# AICatRope_V1_2.net
KiCad netlist of a schematic drawn in Altium Designer
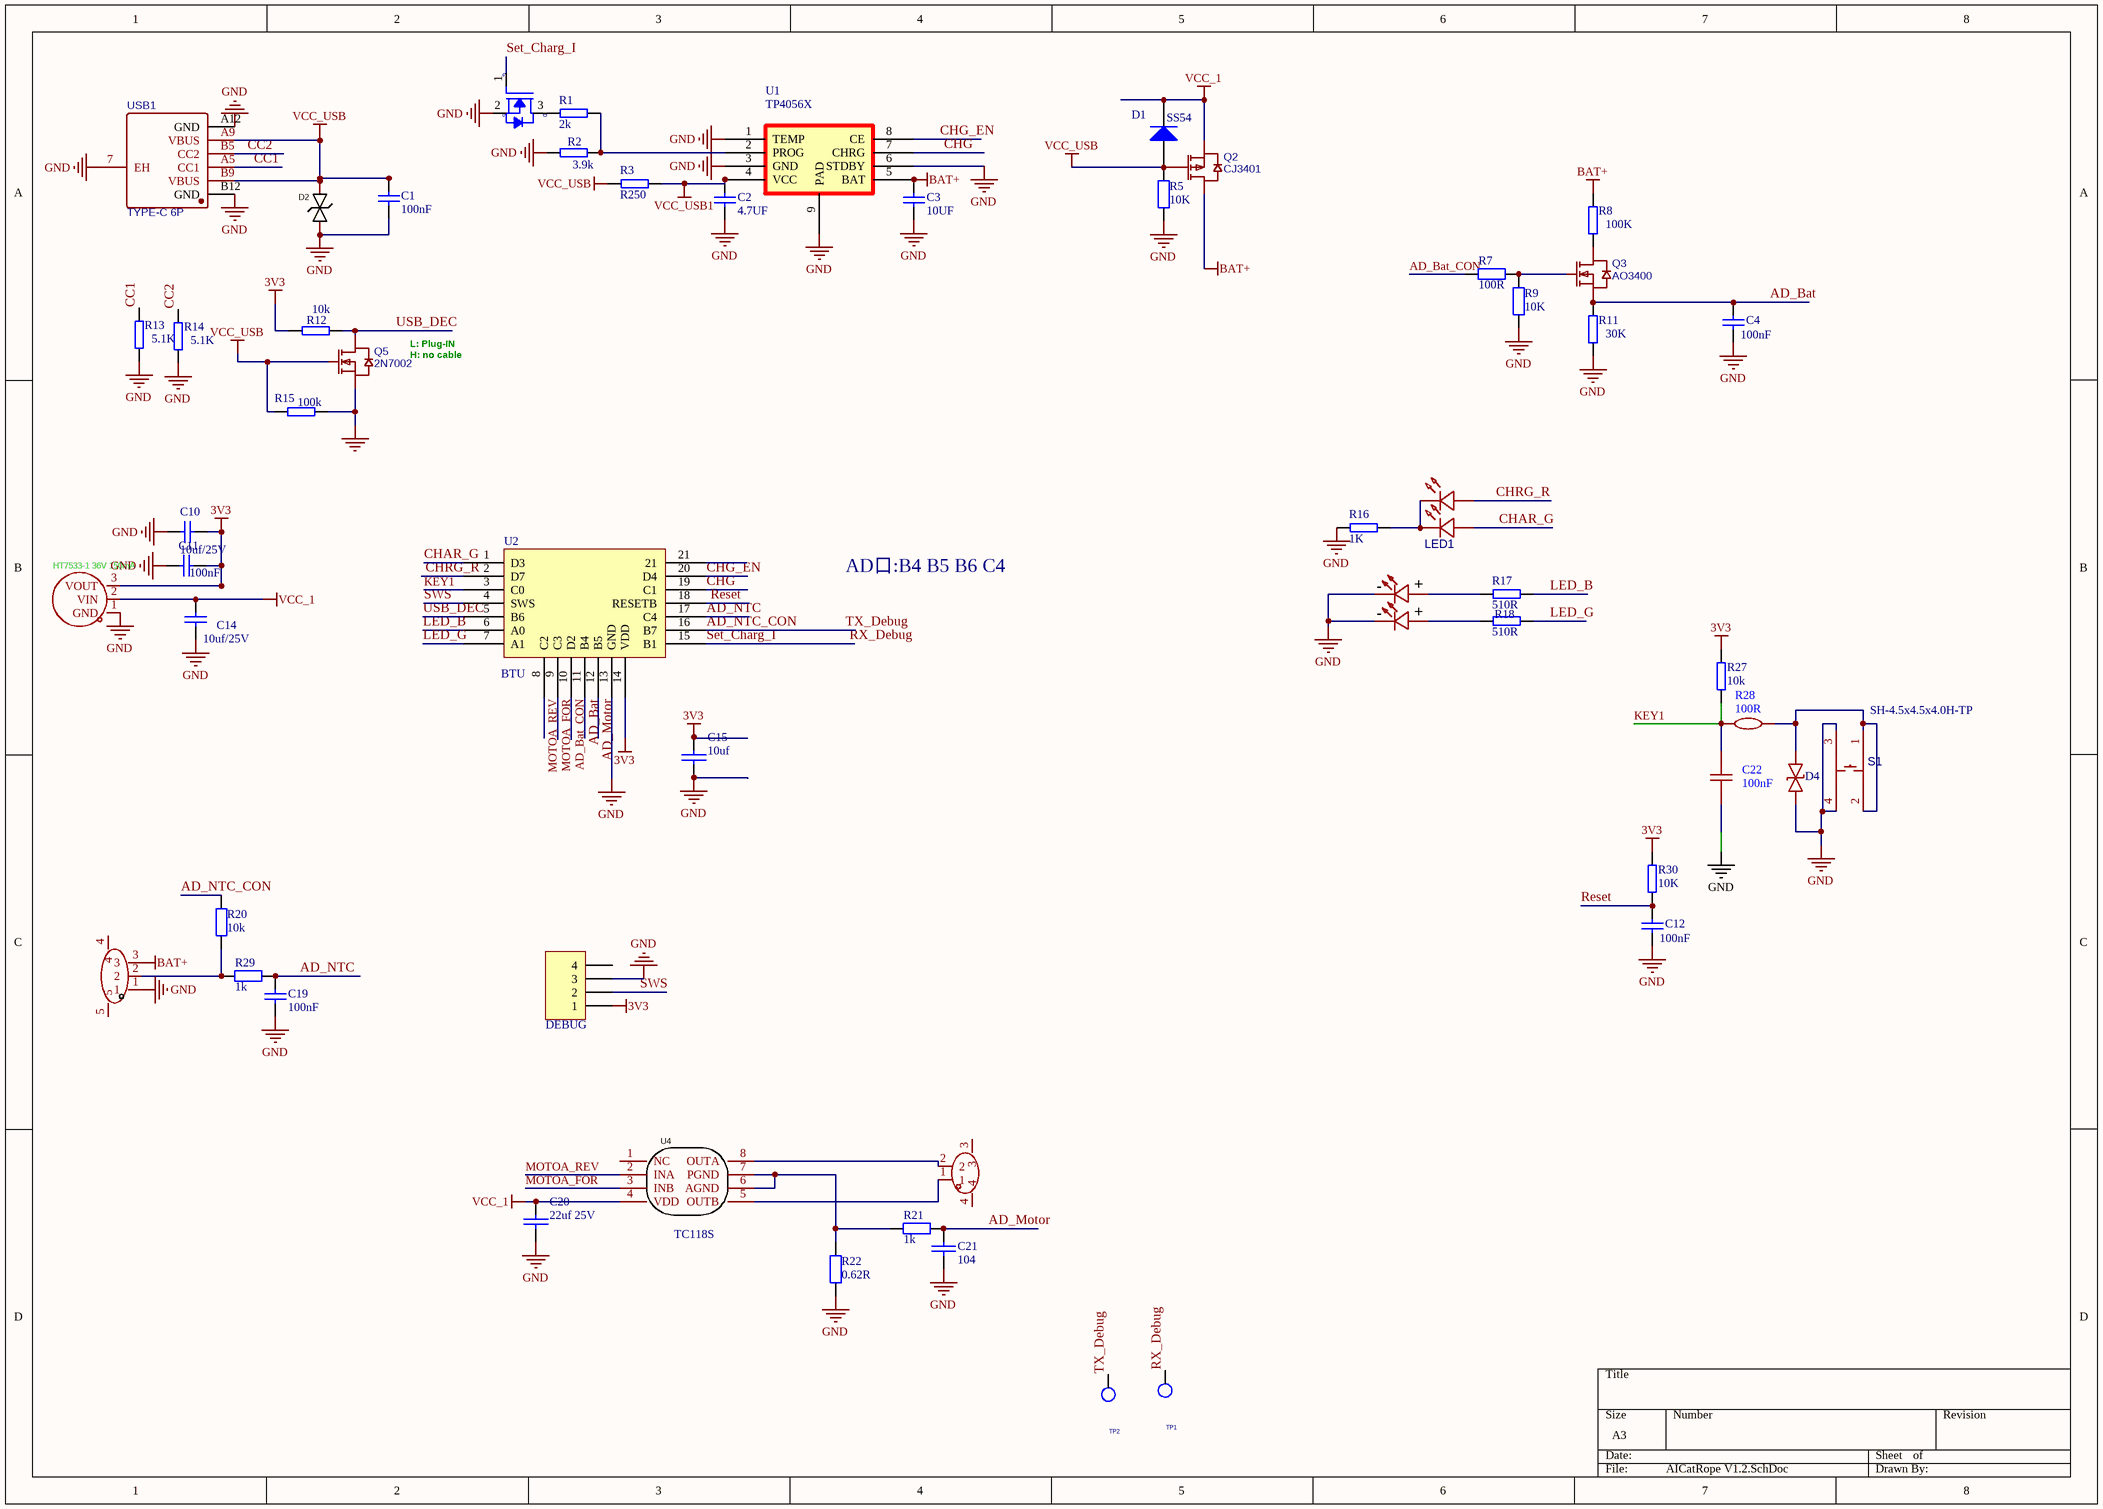
[diagram p0: AICatRope V1.2.SchDoc]

(export (version "E")
  (design (tool "Eeschema 10.0.6"))
  (components
    (comp (ref "BAT1")
      (value "BX-PH2.0-3PWT")
      (footprint "CONN-SMD_2.0-3PLT")
      (libsource (lib "altium-import") (part "root_2_BX-PH2.0-3PWT_"))
    )
    (comp (ref "C1") (value "100nF") (footprint "0603_C") (libsource (lib "DIY") (part "CAP")))
    (comp (ref "C2") (value "4.7UF") (footprint "0603_c") (libsource (lib "DIY") (part "CAP")))
    (comp (ref "C3") (value "10UF") (footprint "0603_c") (libsource (lib "DIY") (part "CAP")))
    (comp (ref "C4") (value "100nF") (footprint "0603_C") (libsource (lib "DIY") (part "CAP")))
    (comp (ref "C10")
      (value "10uf/25V")
      (footprint "0603_c")
      (description "无极电容")
      (libsource (lib "电容电阻电感保险") (part "Cap1"))
    )
    (comp (ref "C11") (value "100nF") (footprint "0603_C") (libsource (lib "DIY") (part "CAP")))
    (comp (ref "C12") (value "100nF") (footprint "0603_C") (libsource (lib "DIY") (part "CAP")))
    (comp (ref "C14")
      (value "10uf/25V")
      (footprint "0603_c")
      (description "无极电容")
      (libsource (lib "电容电阻电感保险") (part "Cap1"))
    )
    (comp (ref "C15")
      (value "10uf")
      (footprint "0603_c")
      (description "C-?-K-0603")
      (libsource (lib "HJ_AD_SchLib") (part "C-0603"))
    )
    (comp (ref "C19") (value "100nF") (footprint "0603_C") (libsource (lib "DIY") (part "CAP")))
    (comp (ref "C20")
      (value "22uf 25V")
      (footprint "0805_C")
      (description "C-?-K-0603")
      (libsource (lib "HJ_AD_SchLib") (part "C-0603"))
    )
    (comp (ref "C21")
      (value "104")
      (footprint "0603_C")
      (description "Capacitor")
      (libsource (lib "*") (part "CAP"))
    )
    (comp (ref "C22")
      (value "100nF")
      (footprint "0603_c")
      (libsource (lib "altium-import") (part "root_1_CAP_0603_"))
    )
    (comp (ref "CN1")
      (value "2.0-2P WT")
      (footprint "CONN-SMD_2.0-2PLT")
      (libsource (lib "altium-import") (part "root_2_mirrored_2.0-2P WT_"))
    )
    (comp (ref "D1")
      (value "SS54")
      (footprint "SMA")
      (description "High Conductance Fast Diode")
      (fields (field (name "PUBLISHER") "Altium Limited"))
      (libsource (lib "Miscellaneous Devices") (part "Diode 1N4148"))
    )
    (comp (ref "D2")
      (value "SMF6.0CA")
      (footprint "SOD-123 双向")
      (fields (field (name "MANUFACTURER PART") "SMF5.0CA"))
      (libsource (lib "altium-import") (part "root_1_SMF5.0CA_C726939_"))
    )
    (comp (ref "D4")
      (value "~")
      (footprint "SOD-523_L1.2-W0.8-LS1.6-RD")
      (fields (field (name "MANUFACTURER PART") "LESD5Z5.0CT1G"))
      (libsource (lib "altium-import") (part "root_1_LESD5Z5.0CT1G_"))
    )
    (comp (ref "LED1")
      (value "XL-3216SURUGC")
      (footprint "LED-SMD_4P-L3.2-W1.6-TL_XL-3216SURUGC")
      (libsource (lib "altium-import") (part "root_0_TJ-S2012SW8TCGLC2R2G-A5_"))
    )
    (comp (ref "LED2")
      (value "tj-s1615sw6tglcbg-a5")
      (footprint "LED-ARRAY-SMD_4P-L1.6-W1.5-TR-RD_TJ-S1615SW6TGLCRB-A5")
      (fields (field (name "MANUFACTURERPART") "TJ-S1615SW6TGLCBG-A5"))
      (libsource (lib "altium-import") (part "root_0_tj-s1615sw6tglcbg-a5_"))
    )
    (comp (ref "P1")
      (value "DEBUG")
      (footprint "SIP3-2.54")
      (description "Header, 4-Pin")
      (fields (field (name "PUBLISHER") "Altium Limited"))
      (libsource (lib "Miscellaneous Connectors") (part "Header 4"))
    )
    (comp (ref "Q1") (value "2N7002") (footprint "SOT-23") (libsource (lib "*") (part "AO3400_SOT23")))
    (comp (ref "Q2")
      (value "CJ3401")
      (footprint "SOT-23")
      (fields (field (name "BOM_SUPPLIER PART") "C13799"))
      (libsource (lib "altium-import") (part "root_2_mirrored_CJ3401_"))
    )
    (comp (ref "Q3")
      (value "AO3400")
      (footprint "SOT-23")
      (fields
        (field (name "BOM_SUPPLIER PART") "C2890442")
        (field (name "BOM_MANUFACTURER PART") "JMTL3400A")
        (field (name "CONTRIBUTOR") "LCSC")
      )
      (libsource (lib "altium-import") (part "root_0_JMTL3400A_"))
    )
    (comp (ref "Q5")
      (value "2N7002")
      (footprint "SOT-23")
      (fields
        (field (name "BOM_SUPPLIER PART") "C2890442")
        (field (name "BOM_MANUFACTURER PART") "JMTL3400A")
        (field (name "CONTRIBUTOR") "LCSC")
      )
      (libsource (lib "altium-import") (part "root_0_JMTL3400A_"))
    )
    (comp (ref "R1") (value "2k") (footprint "0603_R") (libsource (lib "DIY") (part "RES")))
    (comp (ref "R2") (value "3.9k") (footprint "0603_R") (libsource (lib "DIY") (part "RES")))
    (comp (ref "R3") (value "R250") (footprint "1206_R") (libsource (lib "DIY") (part "RES")))
    (comp (ref "R5")
      (value "10K")
      (footprint "0603_R")
      (description "Resistor")
      (fields (field (name "PUBLISHER") "Altium Limited"))
      (libsource (lib "") (part "Res2_2"))
    )
    (comp (ref "R7")
      (value "100R")
      (footprint "0603_r")
      (description "Resistor")
      (fields (field (name "PUBLISHER") "Altium Limited"))
      (libsource (lib "") (part "Res2_3"))
    )
    (comp (ref "R8") (value "100K") (footprint "0603_R") (libsource (lib "DIY") (part "RES")))
    (comp (ref "R9")
      (value "10K")
      (footprint "0603_r")
      (description "Resistor")
      (fields (field (name "PUBLISHER") "Altium Limited"))
      (libsource (lib "*") (part "Res2"))
    )
    (comp (ref "R11") (value "30K") (footprint "0603_R") (libsource (lib "DIY") (part "RES")))
    (comp (ref "R12") (value "10k") (footprint "0603_R") (libsource (lib "DIY") (part "RES")))
    (comp (ref "R13") (value "5.1K") (footprint "0603_R") (libsource (lib "DIY") (part "RES")))
    (comp (ref "R14") (value "5.1K") (footprint "0603_R") (libsource (lib "DIY") (part "RES")))
    (comp (ref "R15") (value "100k") (footprint "0603_R") (libsource (lib "DIY") (part "RES")))
    (comp (ref "R16") (value "1K") (footprint "0603_R") (libsource (lib "DIY") (part "RES")))
    (comp (ref "R17") (value "510R") (footprint "0603_R") (libsource (lib "DIY") (part "RES")))
    (comp (ref "R18") (value "510R") (footprint "0603_R") (libsource (lib "DIY") (part "RES")))
    (comp (ref "R20")
      (value "10k")
      (footprint "0603_R")
      (description "Resistor")
      (fields (field (name "PUBLISHER") "Altium Limited"))
      (libsource (lib "") (part "Res2_2"))
    )
    (comp (ref "R21")
      (value "1k")
      (footprint "0603_R")
      (description "Resistor")
      (fields (field (name "PUBLISHER") "Altium Limited"))
      (libsource (lib "") (part "Res2_1"))
    )
    (comp (ref "R22")
      (value "0.62R")
      (footprint "1206_r")
      (description "Resistor")
      (fields (field (name "PUBLISHER") "Altium Limited"))
      (libsource (lib "") (part "Res2_2"))
    )
    (comp (ref "R27") (value "10k") (footprint "0603_R") (libsource (lib "DIY") (part "RES")))
    (comp (ref "R28")
      (value "100R")
      (footprint "0603_r")
      (libsource (lib "altium-import") (part "root_2_Res_0603_"))
    )
    (comp (ref "R29")
      (value "1k")
      (footprint "0603_R")
      (description "Resistor")
      (fields (field (name "PUBLISHER") "Altium Limited"))
      (libsource (lib "") (part "Res2_1"))
    )
    (comp (ref "R30") (value "10K") (footprint "0603_R") (libsource (lib "DIY") (part "RES")))
    (comp (ref "S1")
      (value "SH-4.5x4.5x4.0H-TP")
      (footprint "SW-SMD_4P-SH-4.5X4.5X4.0H-TP")
      (libsource (lib "altium-import") (part "root_3_TS-1002S-05026C_"))
    )
    (comp (ref "TP1") (value "~") (footprint "TP") (libsource (lib "*") (part "T POINT R")))
    (comp (ref "TP2") (value "~") (footprint "TP") (libsource (lib "*") (part "T POINT R")))
    (comp (ref "U1")
      (value "TP4056X")
      (footprint "SOP8-9")
      (description "TP4056")
      (libsource (lib "芯片") (part "TP4056"))
    )
    (comp (ref "U2") (value "BTU") (footprint "BTU") (libsource (lib "MyLib") (part "BTU")))
    (comp (ref "U3")
      (value "HT7533-1 36V 150mA")
      (footprint "SOT-89_L4.5-W2.5-P1.50-LS4.2-BR")
      (fields (field (name "MANUFACTURER PART") "HT7533-1"))
      (libsource (lib "altium-import") (part "root_2_HT7533-1_C347186_"))
    )
    (comp (ref "U4")
      (value "TC118S")
      (footprint "SOP8-9")
      (libsource (lib "altium-import") (part "root_0_TC118S_"))
    )
    (comp (ref "USB1")
      (value "TYPE-C 6P")
      (footprint "TPYE-C-6")
      (fields (field (name "BOM_SUPPLIER PART") "C456012") (field (name "CONTRIBUTOR") "LCSC"))
      (libsource (lib "altium-import") (part "root_2_TYPE-C 6P_"))
    )
  )
  (nets
    (net (code "1") (name "/AD_Bat") (class "Default")
      (node (ref "C4") (pin "2") (pintype "passive"))
      (node (ref "Q3") (pin "2") (pinfunction "S_2") (pintype "passive"))
      (node (ref "R11") (pin "1") (pinfunction "1_1") (pintype "passive"))
      (node (ref "U2") (pin "11") (pinfunction "B4_11") (pintype "passive"))
    )
    (net (code "2") (name "/AD_Bat_CON") (class "Default")
      (node (ref "R7") (pin "2") (pinfunction "2_2") (pintype "passive"))
      (node (ref "U2") (pin "10") (pinfunction "D2_10") (pintype "passive"))
    )
    (net (code "3") (name "/AD_Motor") (class "Default")
      (node (ref "C21") (pin "2") (pinfunction "2_2") (pintype "passive"))
      (node (ref "R21") (pin "1") (pinfunction "1_1") (pintype "passive"))
      (node (ref "U2") (pin "12") (pinfunction "B5_12") (pintype "passive"))
    )
    (net (code "4") (name "/AD_NTC") (class "Default")
      (node (ref "C19") (pin "1") (pintype "passive"))
      (node (ref "R29") (pin "1") (pinfunction "1_1") (pintype "passive"))
      (node (ref "U2") (pin "17") (pinfunction "C4_17") (pintype "passive"))
    )
    (net (code "5") (name "/AD_NTC_CON") (class "Default")
      (node (ref "R20") (pin "2") (pinfunction "2_2") (pintype "passive"))
      (node (ref "TP2") (pin "1") (pinfunction "TP_1") (pintype "passive"))
      (node (ref "U2") (pin "16") (pinfunction "B7_16") (pintype "passive"))
    )
    (net (code "6") (name "/CC1") (class "Default")
      (node (ref "R13") (pin "1") (pinfunction "1_1") (pintype "passive"))
      (node (ref "USB1") (pin "A5") (pinfunction "CC1_A5") (pintype "passive"))
    )
    (net (code "7") (name "/CC2") (class "Default")
      (node (ref "R14") (pin "1") (pinfunction "1_1") (pintype "passive"))
      (node (ref "USB1") (pin "B5") (pinfunction "CC2_B5") (pintype "passive"))
    )
    (net (code "8") (name "/CHAR_G") (class "Default")
      (node (ref "LED1") (pin "3") (pinfunction "A_3") (pintype "passive"))
      (node (ref "U2") (pin "1") (pinfunction "D3_1") (pintype "passive"))
    )
    (net (code "9") (name "/CHG") (class "Default")
      (node (ref "U1") (pin "7") (pinfunction "CHRG_7") (pintype "passive"))
      (node (ref "U2") (pin "19") (pinfunction "C1_19") (pintype "passive"))
    )
    (net (code "10") (name "/CHG_EN") (class "Default")
      (node (ref "U1") (pin "8") (pinfunction "CE_8") (pintype "passive"))
      (node (ref "U2") (pin "20") (pinfunction "D4_20") (pintype "passive"))
    )
    (net (code "11") (name "/CHRG_R") (class "Default")
      (node (ref "LED1") (pin "1") (pinfunction "A_1") (pintype "passive"))
      (node (ref "U2") (pin "2") (pinfunction "D7_2") (pintype "passive"))
    )
    (net (code "12") (name "/KEY1") (class "Default")
      (node (ref "C22") (pin "2") (pinfunction "2_2") (pintype "passive"))
      (node (ref "R27") (pin "1") (pinfunction "1_1") (pintype "passive"))
      (node (ref "R28") (pin "2") (pinfunction "2_2") (pintype "passive"))
      (node (ref "U2") (pin "3") (pinfunction "C0_3") (pintype "passive"))
    )
    (net (code "13") (name "/LED_B") (class "Default")
      (node (ref "R17") (pin "2") (pinfunction "2_2") (pintype "passive"))
      (node (ref "U2") (pin "6") (pinfunction "A0_6") (pintype "passive"))
    )
    (net (code "14") (name "/LED_G") (class "Default")
      (node (ref "R18") (pin "2") (pinfunction "2_2") (pintype "passive"))
      (node (ref "U2") (pin "7") (pinfunction "A1_7") (pintype "passive"))
    )
    (net (code "15") (name "/MOTOA_FOR") (class "Default")
      (node (ref "U2") (pin "9") (pinfunction "C3_9") (pintype "passive"))
      (node (ref "U4") (pin "3") (pinfunction "INB_3") (pintype "passive"))
    )
    (net (code "16") (name "/MOTOA_REV") (class "Default")
      (node (ref "U2") (pin "8") (pinfunction "C2_8") (pintype "passive"))
      (node (ref "U4") (pin "2") (pinfunction "INA_2") (pintype "passive"))
    )
    (net (code "17") (name "/RX_Debug") (class "Default")
      (node (ref "Q1") (pin "1") (pinfunction "GATE_1") (pintype "passive"))
      (node (ref "TP1") (pin "1") (pinfunction "TP_1") (pintype "passive"))
      (node (ref "U2") (pin "15") (pinfunction "B1_15") (pintype "passive"))
    )
    (net (code "18") (name "/Reset") (class "Default")
      (node (ref "C12") (pin "2") (pintype "passive"))
      (node (ref "R30") (pin "2") (pinfunction "2_2") (pintype "passive"))
      (node (ref "U2") (pin "18") (pinfunction "RESETB_18") (pintype "passive"))
    )
    (net (code "19") (name "/SWS") (class "Default")
      (node (ref "P1") (pin "2") (pinfunction "2_2") (pintype "passive"))
      (node (ref "U2") (pin "4") (pinfunction "SWS_4") (pintype "passive"))
    )
    (net (code "20") (name "/USB_DEC") (class "Default")
      (node (ref "Q5") (pin "3") (pinfunction "D_3") (pintype "passive"))
      (node (ref "R12") (pin "2") (pinfunction "2_2") (pintype "passive"))
      (node (ref "U2") (pin "5") (pinfunction "B6_5") (pintype "passive"))
    )
    (net (code "21") (name "3V3") (class "Default")
      (node (ref "C10") (pin "2") (pinfunction "2_2") (pintype "passive"))
      (node (ref "C11") (pin "1") (pintype "passive"))
      (node (ref "C15") (pin "2") (pinfunction "2_2") (pintype "passive"))
      (node (ref "P1") (pin "1") (pinfunction "1_1") (pintype "passive"))
      (node (ref "R12") (pin "1") (pinfunction "1_1") (pintype "passive"))
      (node (ref "R27") (pin "2") (pinfunction "2_2") (pintype "passive"))
      (node (ref "R30") (pin "1") (pinfunction "1_1") (pintype "passive"))
      (node (ref "U2") (pin "14") (pinfunction "VDD_14") (pintype "passive"))
      (node (ref "U3") (pin "3") (pinfunction "VOUT_3") (pintype "passive"))
    )
    (net (code "22") (name "BAT+") (class "Default")
      (node (ref "BAT1") (pin "3") (pinfunction "3_3") (pintype "passive"))
      (node (ref "C3") (pin "2") (pintype "passive"))
      (node (ref "Q2") (pin "3") (pinfunction "D_3") (pintype "passive"))
      (node (ref "R8") (pin "1") (pinfunction "1_1") (pintype "passive"))
      (node (ref "U1") (pin "5") (pinfunction "BAT_5") (pintype "passive"))
    )
    (net (code "23") (name "GND") (class "Default")
      (node (ref "BAT1") (pin "1") (pinfunction "1_1") (pintype "passive"))
      (node (ref "C1") (pin "2") (pintype "passive"))
      (node (ref "C10") (pin "1") (pinfunction "1_1") (pintype "passive"))
      (node (ref "C11") (pin "2") (pintype "passive"))
      (node (ref "C12") (pin "1") (pintype "passive"))
      (node (ref "C14") (pin "1") (pinfunction "1_1") (pintype "passive"))
      (node (ref "C15") (pin "1") (pinfunction "1_1") (pintype "passive"))
      (node (ref "C19") (pin "2") (pintype "passive"))
      (node (ref "C2") (pin "1") (pintype "passive"))
      (node (ref "C20") (pin "1") (pinfunction "1_1") (pintype "passive"))
      (node (ref "C21") (pin "1") (pinfunction "1_1") (pintype "passive"))
      (node (ref "C22") (pin "1") (pinfunction "1_1") (pintype "passive"))
      (node (ref "C3") (pin "1") (pintype "passive"))
      (node (ref "C4") (pin "1") (pintype "passive"))
      (node (ref "D2") (pin "1") (pinfunction "1_1") (pintype "passive"))
      (node (ref "D4") (pin "1") (pinfunction "1_1") (pintype "passive"))
      (node (ref "LED2") (pin "2") (pinfunction "2_2") (pintype "passive"))
      (node (ref "LED2") (pin "4") (pinfunction "4_4") (pintype "passive"))
      (node (ref "P1") (pin "3") (pinfunction "3_3") (pintype "passive"))
      (node (ref "Q1") (pin "2") (pinfunction "SOURCE_2") (pintype "passive"))
      (node (ref "Q5") (pin "2") (pinfunction "S_2") (pintype "passive"))
      (node (ref "R11") (pin "2") (pinfunction "2_2") (pintype "passive"))
      (node (ref "R13") (pin "2") (pinfunction "2_2") (pintype "passive"))
      (node (ref "R14") (pin "2") (pinfunction "2_2") (pintype "passive"))
      (node (ref "R15") (pin "2") (pinfunction "2_2") (pintype "passive"))
      (node (ref "R16") (pin "1") (pinfunction "1_1") (pintype "passive"))
      (node (ref "R2") (pin "1") (pinfunction "1_1") (pintype "passive"))
      (node (ref "R22") (pin "1") (pinfunction "1_1") (pintype "passive"))
      (node (ref "R5") (pin "1") (pinfunction "1_1") (pintype "passive"))
      (node (ref "R9") (pin "1") (pinfunction "1_1") (pintype "passive"))
      (node (ref "S1") (pin "3") (pinfunction "3_3") (pintype "passive"))
      (node (ref "S1") (pin "4") (pinfunction "4_4") (pintype "passive"))
      (node (ref "U1") (pin "1") (pinfunction "TEMP_1") (pintype "passive"))
      (node (ref "U1") (pin "3") (pinfunction "GND_3") (pintype "passive"))
      (node (ref "U1") (pin "6") (pinfunction "STDBY_6") (pintype "passive"))
      (node (ref "U1") (pin "9") (pinfunction "PAD_9") (pintype "passive"))
      (node (ref "U2") (pin "13") (pinfunction "GND_13") (pintype "passive"))
      (node (ref "U3") (pin "1") (pinfunction "GND_1") (pintype "passive"))
      (node (ref "USB1") (pin "7") (pinfunction "EH_7") (pintype "passive"))
      (node (ref "USB1") (pin "A12") (pinfunction "GND_A12") (pintype "passive"))
      (node (ref "USB1") (pin "B12") (pinfunction "GND_B12") (pintype "passive"))
    )
    (net (code "24") (name "Net-(BAT1-Pad2)") (class "Default")
      (node (ref "BAT1") (pin "2") (pinfunction "2_2") (pintype "passive"))
      (node (ref "R20") (pin "1") (pinfunction "1_1") (pintype "passive"))
      (node (ref "R29") (pin "2") (pinfunction "2_2") (pintype "passive"))
    )
    (net (code "25") (name "Net-(D4-Pad2)") (class "Default")
      (node (ref "D4") (pin "2") (pinfunction "2_2") (pintype "passive"))
      (node (ref "R28") (pin "1") (pinfunction "1_1") (pintype "passive"))
      (node (ref "S1") (pin "1") (pinfunction "1_1") (pintype "passive"))
      (node (ref "S1") (pin "2") (pinfunction "2_2") (pintype "passive"))
    )
    (net (code "26") (name "Net-(LED1-K-Pad2)") (class "Default")
      (node (ref "LED1") (pin "2") (pinfunction "K_2") (pintype "passive"))
      (node (ref "LED1") (pin "4") (pinfunction "K_4") (pintype "passive"))
      (node (ref "R16") (pin "2") (pinfunction "2_2") (pintype "passive"))
    )
    (net (code "27") (name "Net-(LED2-Pad1)") (class "Default")
      (node (ref "LED2") (pin "1") (pinfunction "1_1") (pintype "passive"))
      (node (ref "R17") (pin "1") (pinfunction "1_1") (pintype "passive"))
    )
    (net (code "28") (name "Net-(LED2-Pad3)") (class "Default")
      (node (ref "LED2") (pin "3") (pinfunction "3_3") (pintype "passive"))
      (node (ref "R18") (pin "1") (pinfunction "1_1") (pintype "passive"))
    )
    (net (code "29") (name "Net-(Q1-DRAIN)") (class "Default")
      (node (ref "Q1") (pin "3") (pinfunction "DRAIN_3") (pintype "passive"))
      (node (ref "R1") (pin "1") (pinfunction "1_1") (pintype "passive"))
    )
    (net (code "30") (name "Net-(Q3-D)") (class "Default")
      (node (ref "Q3") (pin "3") (pinfunction "D_3") (pintype "passive"))
      (node (ref "R8") (pin "2") (pinfunction "2_2") (pintype "passive"))
    )
    (net (code "31") (name "Net-(Q3-G)") (class "Default")
      (node (ref "Q3") (pin "1") (pinfunction "G_1") (pintype "passive"))
      (node (ref "R7") (pin "1") (pinfunction "1_1") (pintype "passive"))
      (node (ref "R9") (pin "2") (pinfunction "2_2") (pintype "passive"))
    )
    (net (code "32") (name "Net-(U1-PROG)") (class "Default")
      (node (ref "R1") (pin "2") (pinfunction "2_2") (pintype "passive"))
      (node (ref "R2") (pin "2") (pinfunction "2_2") (pintype "passive"))
      (node (ref "U1") (pin "2") (pinfunction "PROG_2") (pintype "passive"))
    )
    (net (code "33") (name "Net-(U4-AGND)") (class "Default")
      (node (ref "R21") (pin "2") (pinfunction "2_2") (pintype "passive"))
      (node (ref "R22") (pin "2") (pinfunction "2_2") (pintype "passive"))
      (node (ref "U4") (pin "6") (pinfunction "AGND_6") (pintype "passive"))
      (node (ref "U4") (pin "7") (pinfunction "PGND_7") (pintype "passive"))
    )
    (net (code "34") (name "Net-(U4-OUTA)") (class "Default")
      (node (ref "CN1") (pin "2") (pinfunction "2_2") (pintype "passive"))
      (node (ref "U4") (pin "8") (pinfunction "OUTA_8") (pintype "passive"))
    )
    (net (code "35") (name "Net-(U4-OUTB)") (class "Default")
      (node (ref "CN1") (pin "1") (pinfunction "1_1") (pintype "passive"))
      (node (ref "U4") (pin "5") (pinfunction "OUTB_5") (pintype "passive"))
    )
    (net (code "36") (name "VCC_1") (class "Default")
      (node (ref "C14") (pin "2") (pinfunction "2_2") (pintype "passive"))
      (node (ref "C20") (pin "2") (pinfunction "2_2") (pintype "passive"))
      (node (ref "D1") (pin "2") (pinfunction "K_2") (pintype "passive"))
      (node (ref "Q2") (pin "2") (pinfunction "S_2") (pintype "passive"))
      (node (ref "U3") (pin "2") (pinfunction "VIN_2") (pintype "passive"))
      (node (ref "U4") (pin "4") (pinfunction "VDD_4") (pintype "passive"))
    )
    (net (code "37") (name "VCC_USB") (class "Default")
      (node (ref "C1") (pin "1") (pintype "passive"))
      (node (ref "D1") (pin "1") (pinfunction "A_1") (pintype "passive"))
      (node (ref "D2") (pin "2") (pinfunction "2_2") (pintype "passive"))
      (node (ref "Q2") (pin "1") (pinfunction "G_1") (pintype "passive"))
      (node (ref "Q5") (pin "1") (pinfunction "G_1") (pintype "passive"))
      (node (ref "R15") (pin "1") (pinfunction "1_1") (pintype "passive"))
      (node (ref "R3") (pin "2") (pinfunction "2_2") (pintype "passive"))
      (node (ref "R5") (pin "2") (pinfunction "2_2") (pintype "passive"))
      (node (ref "USB1") (pin "A9") (pinfunction "VBUS_A9") (pintype "passive"))
      (node (ref "USB1") (pin "B9") (pinfunction "VBUS_B9") (pintype "passive"))
    )
    (net (code "38") (name "VCC_USB1") (class "Default")
      (node (ref "C2") (pin "2") (pintype "passive"))
      (node (ref "R3") (pin "1") (pinfunction "1_1") (pintype "passive"))
      (node (ref "U1") (pin "4") (pinfunction "VCC_4") (pintype "passive"))
    )
    (net (code "39") (name "unconnected-(BAT1-Pad4)") (class "Default")
      (node (ref "BAT1") (pin "4") (pinfunction "4_4") (pintype "passive"))
    )
    (net (code "40") (name "unconnected-(BAT1-Pad5)") (class "Default")
      (node (ref "BAT1") (pin "5") (pinfunction "5_5") (pintype "passive"))
    )
    (net (code "41") (name "unconnected-(CN1-Pad3)") (class "Default")
      (node (ref "CN1") (pin "3") (pinfunction "3_3") (pintype "passive"))
    )
    (net (code "42") (name "unconnected-(CN1-Pad4)") (class "Default")
      (node (ref "CN1") (pin "4") (pinfunction "4_4") (pintype "passive"))
    )
    (net (code "43") (name "unconnected-(P1-Pad4)") (class "Default")
      (node (ref "P1") (pin "4") (pinfunction "4_4") (pintype "passive"))
    )
    (net (code "44") (name "unconnected-(U2-Pad21)") (class "Default")
      (node (ref "U2") (pin "21") (pinfunction "21_21") (pintype "passive"))
    )
    (net (code "45") (name "unconnected-(U4-NC-Pad1)") (class "Default")
      (node (ref "U4") (pin "1") (pinfunction "NC_1") (pintype "passive"))
    )
  )
)
